# Smart_Motor_Switch.net
KiCad netlist of a schematic drawn in Altium Designer
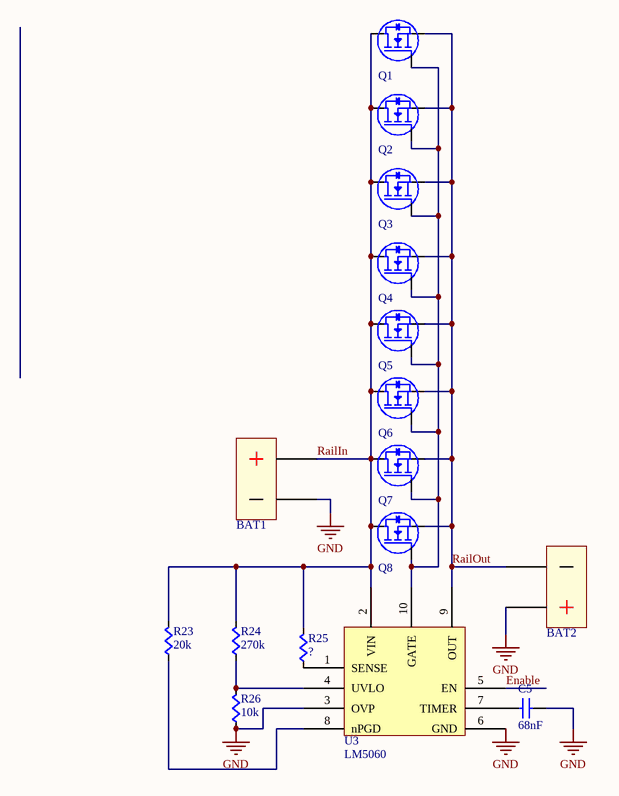
[diagram p0: Smart Motor Switch.SchDoc]

(export (version "E")
  (design (tool "Eeschema 10.0.6"))
  (components
    (comp (ref "BAT1")
      (value "BATWIRE")
      (footprint "BATWIRE12")
      (description "Two large gauge leads soldered directly to the board.")
      (libsource (lib "") (part "BATWIRE_1"))
    )
    (comp (ref "BAT2")
      (value "BATWIRE")
      (footprint "BATWIRE12")
      (description "Two large gauge leads soldered directly to the board.")
      (libsource (lib "SubjuGator8") (part "BATWIRE"))
    )
    (comp (ref "C5")
      (value "68nF")
      (footprint "CAPC0603")
      (fields (field (name "Comment") "Cap"))
      (libsource (lib "SubjuGator8") (part "Cap"))
    )
    (comp (ref "Q1")
      (value "CSD19502Q5B")
      (footprint "CSD19502Q5B")
      (description "NEXFET Power MOSFET")
      (libsource (lib "SubjuGator8") (part "CSD19502Q5B"))
    )
    (comp (ref "Q2")
      (value "CSD19502Q5B")
      (footprint "CSD19502Q5B")
      (description "NEXFET Power MOSFET")
      (libsource (lib "SubjuGator8") (part "CSD19502Q5B"))
    )
    (comp (ref "Q3")
      (value "CSD19502Q5B")
      (footprint "CSD19502Q5B")
      (description "NEXFET Power MOSFET")
      (libsource (lib "SubjuGator8") (part "CSD19502Q5B"))
    )
    (comp (ref "Q4")
      (value "CSD19502Q5B")
      (footprint "CSD19502Q5B")
      (description "NEXFET Power MOSFET")
      (libsource (lib "SubjuGator8") (part "CSD19502Q5B"))
    )
    (comp (ref "Q5")
      (value "CSD19502Q5B")
      (footprint "CSD19502Q5B")
      (description "NEXFET Power MOSFET")
      (libsource (lib "SubjuGator8") (part "CSD19502Q5B"))
    )
    (comp (ref "Q6")
      (value "CSD19502Q5B")
      (footprint "CSD19502Q5B")
      (description "NEXFET Power MOSFET")
      (libsource (lib "SubjuGator8") (part "CSD19502Q5B"))
    )
    (comp (ref "Q7")
      (value "CSD19502Q5B")
      (footprint "CSD19502Q5B")
      (description "NEXFET Power MOSFET")
      (libsource (lib "SubjuGator8") (part "CSD19502Q5B"))
    )
    (comp (ref "Q8")
      (value "CSD19502Q5B")
      (footprint "CSD19502Q5B")
      (description "NEXFET Power MOSFET")
      (libsource (lib "SubjuGator8") (part "CSD19502Q5B"))
    )
    (comp (ref "R23")
      (value "20k")
      (footprint "RES0603")
      (fields (field (name "Comment") "Res"))
      (libsource (lib "SubjuGator8") (part "Res"))
    )
    (comp (ref "R24")
      (value "270k")
      (footprint "RES0603")
      (fields (field (name "Comment") "Res"))
      (libsource (lib "SubjuGator8") (part "Res"))
    )
    (comp (ref "R25")
      (value "?")
      (footprint "RES0603")
      (fields (field (name "Comment") "Res"))
      (libsource (lib "SubjuGator8") (part "Res"))
    )
    (comp (ref "R26")
      (value "10k")
      (footprint "RES0603")
      (fields (field (name "Comment") "Res"))
      (libsource (lib "SubjuGator8") (part "Res"))
    )
    (comp (ref "U3")
      (value "LM5060")
      (footprint "LM5060")
      (description "Hotswap Controller")
      (libsource (lib "SubjuGator8") (part "LM5060"))
    )
  )
  (nets
    (net (code "1") (name "/Enable") (class "Default")
      (node (ref "U3") (pin "5") (pinfunction "EN_5") (pintype "passive"))
    )
    (net (code "2") (name "/RailIn") (class "Default")
      (node (ref "BAT1") (pin "+") (pinfunction "+_+") (pintype "power_in"))
      (node (ref "Q1") (pin "D") (pinfunction "D_D") (pintype "passive"))
      (node (ref "Q2") (pin "D") (pinfunction "D_D") (pintype "passive"))
      (node (ref "Q3") (pin "D") (pinfunction "D_D") (pintype "passive"))
      (node (ref "Q4") (pin "D") (pinfunction "D_D") (pintype "passive"))
      (node (ref "Q5") (pin "D") (pinfunction "D_D") (pintype "passive"))
      (node (ref "Q6") (pin "D") (pinfunction "D_D") (pintype "passive"))
      (node (ref "Q7") (pin "D") (pinfunction "D_D") (pintype "passive"))
      (node (ref "Q8") (pin "D") (pinfunction "D_D") (pintype "passive"))
      (node (ref "R23") (pin "1") (pinfunction "A_1") (pintype "passive"))
      (node (ref "R24") (pin "1") (pinfunction "A_1") (pintype "passive"))
      (node (ref "R25") (pin "1") (pinfunction "A_1") (pintype "passive"))
      (node (ref "U3") (pin "2") (pinfunction "VIN_2") (pintype "passive"))
    )
    (net (code "3") (name "/RailOut") (class "Default")
      (node (ref "BAT2") (pin "-") (pinfunction "-_-") (pintype "power_in"))
      (node (ref "Q1") (pin "S") (pinfunction "S_S") (pintype "passive"))
      (node (ref "Q2") (pin "S") (pinfunction "S_S") (pintype "passive"))
      (node (ref "Q3") (pin "S") (pinfunction "S_S") (pintype "passive"))
      (node (ref "Q4") (pin "S") (pinfunction "S_S") (pintype "passive"))
      (node (ref "Q5") (pin "S") (pinfunction "S_S") (pintype "passive"))
      (node (ref "Q6") (pin "S") (pinfunction "S_S") (pintype "passive"))
      (node (ref "Q7") (pin "S") (pinfunction "S_S") (pintype "passive"))
      (node (ref "Q8") (pin "S") (pinfunction "S_S") (pintype "passive"))
      (node (ref "U3") (pin "9") (pinfunction "OUT_9") (pintype "passive"))
    )
    (net (code "4") (name "GND") (class "Default")
      (node (ref "BAT1") (pin "-") (pinfunction "-_-") (pintype "power_in"))
      (node (ref "BAT2") (pin "+") (pinfunction "+_+") (pintype "power_in"))
      (node (ref "C5") (pin "2") (pinfunction "B_2") (pintype "passive"))
      (node (ref "R26") (pin "2") (pinfunction "B_2") (pintype "passive"))
      (node (ref "U3") (pin "3") (pinfunction "OVP_3") (pintype "passive"))
      (node (ref "U3") (pin "6") (pinfunction "GND_6") (pintype "passive"))
    )
    (net (code "5") (name "Net-(C5-A)") (class "Default")
      (node (ref "C5") (pin "1") (pinfunction "A_1") (pintype "passive"))
      (node (ref "U3") (pin "7") (pinfunction "TIMER_7") (pintype "passive"))
    )
    (net (code "6") (name "Net-(R23-B)") (class "Default")
      (node (ref "R23") (pin "2") (pinfunction "B_2") (pintype "passive"))
      (node (ref "U3") (pin "8") (pinfunction "nPGD_8") (pintype "passive"))
    )
    (net (code "7") (name "Net-(R24-B)") (class "Default")
      (node (ref "R24") (pin "2") (pinfunction "B_2") (pintype "passive"))
      (node (ref "R26") (pin "1") (pinfunction "A_1") (pintype "passive"))
      (node (ref "U3") (pin "4") (pinfunction "UVLO_4") (pintype "passive"))
    )
    (net (code "8") (name "Net-(R25-B)") (class "Default")
      (node (ref "R25") (pin "2") (pinfunction "B_2") (pintype "passive"))
      (node (ref "U3") (pin "1") (pinfunction "SENSE_1") (pintype "passive"))
    )
    (net (code "9") (name "Net-(U3-GATE)") (class "Default")
      (node (ref "Q1") (pin "G") (pinfunction "G_G") (pintype "passive"))
      (node (ref "Q2") (pin "G") (pinfunction "G_G") (pintype "passive"))
      (node (ref "Q3") (pin "G") (pinfunction "G_G") (pintype "passive"))
      (node (ref "Q4") (pin "G") (pinfunction "G_G") (pintype "passive"))
      (node (ref "Q5") (pin "G") (pinfunction "G_G") (pintype "passive"))
      (node (ref "Q6") (pin "G") (pinfunction "G_G") (pintype "passive"))
      (node (ref "Q7") (pin "G") (pinfunction "G_G") (pintype "passive"))
      (node (ref "Q8") (pin "G") (pinfunction "G_G") (pintype "passive"))
      (node (ref "U3") (pin "10") (pinfunction "GATE_10") (pintype "passive"))
    )
  )
)
